# main.net
KiCad netlist of a schematic drawn in EAGLE
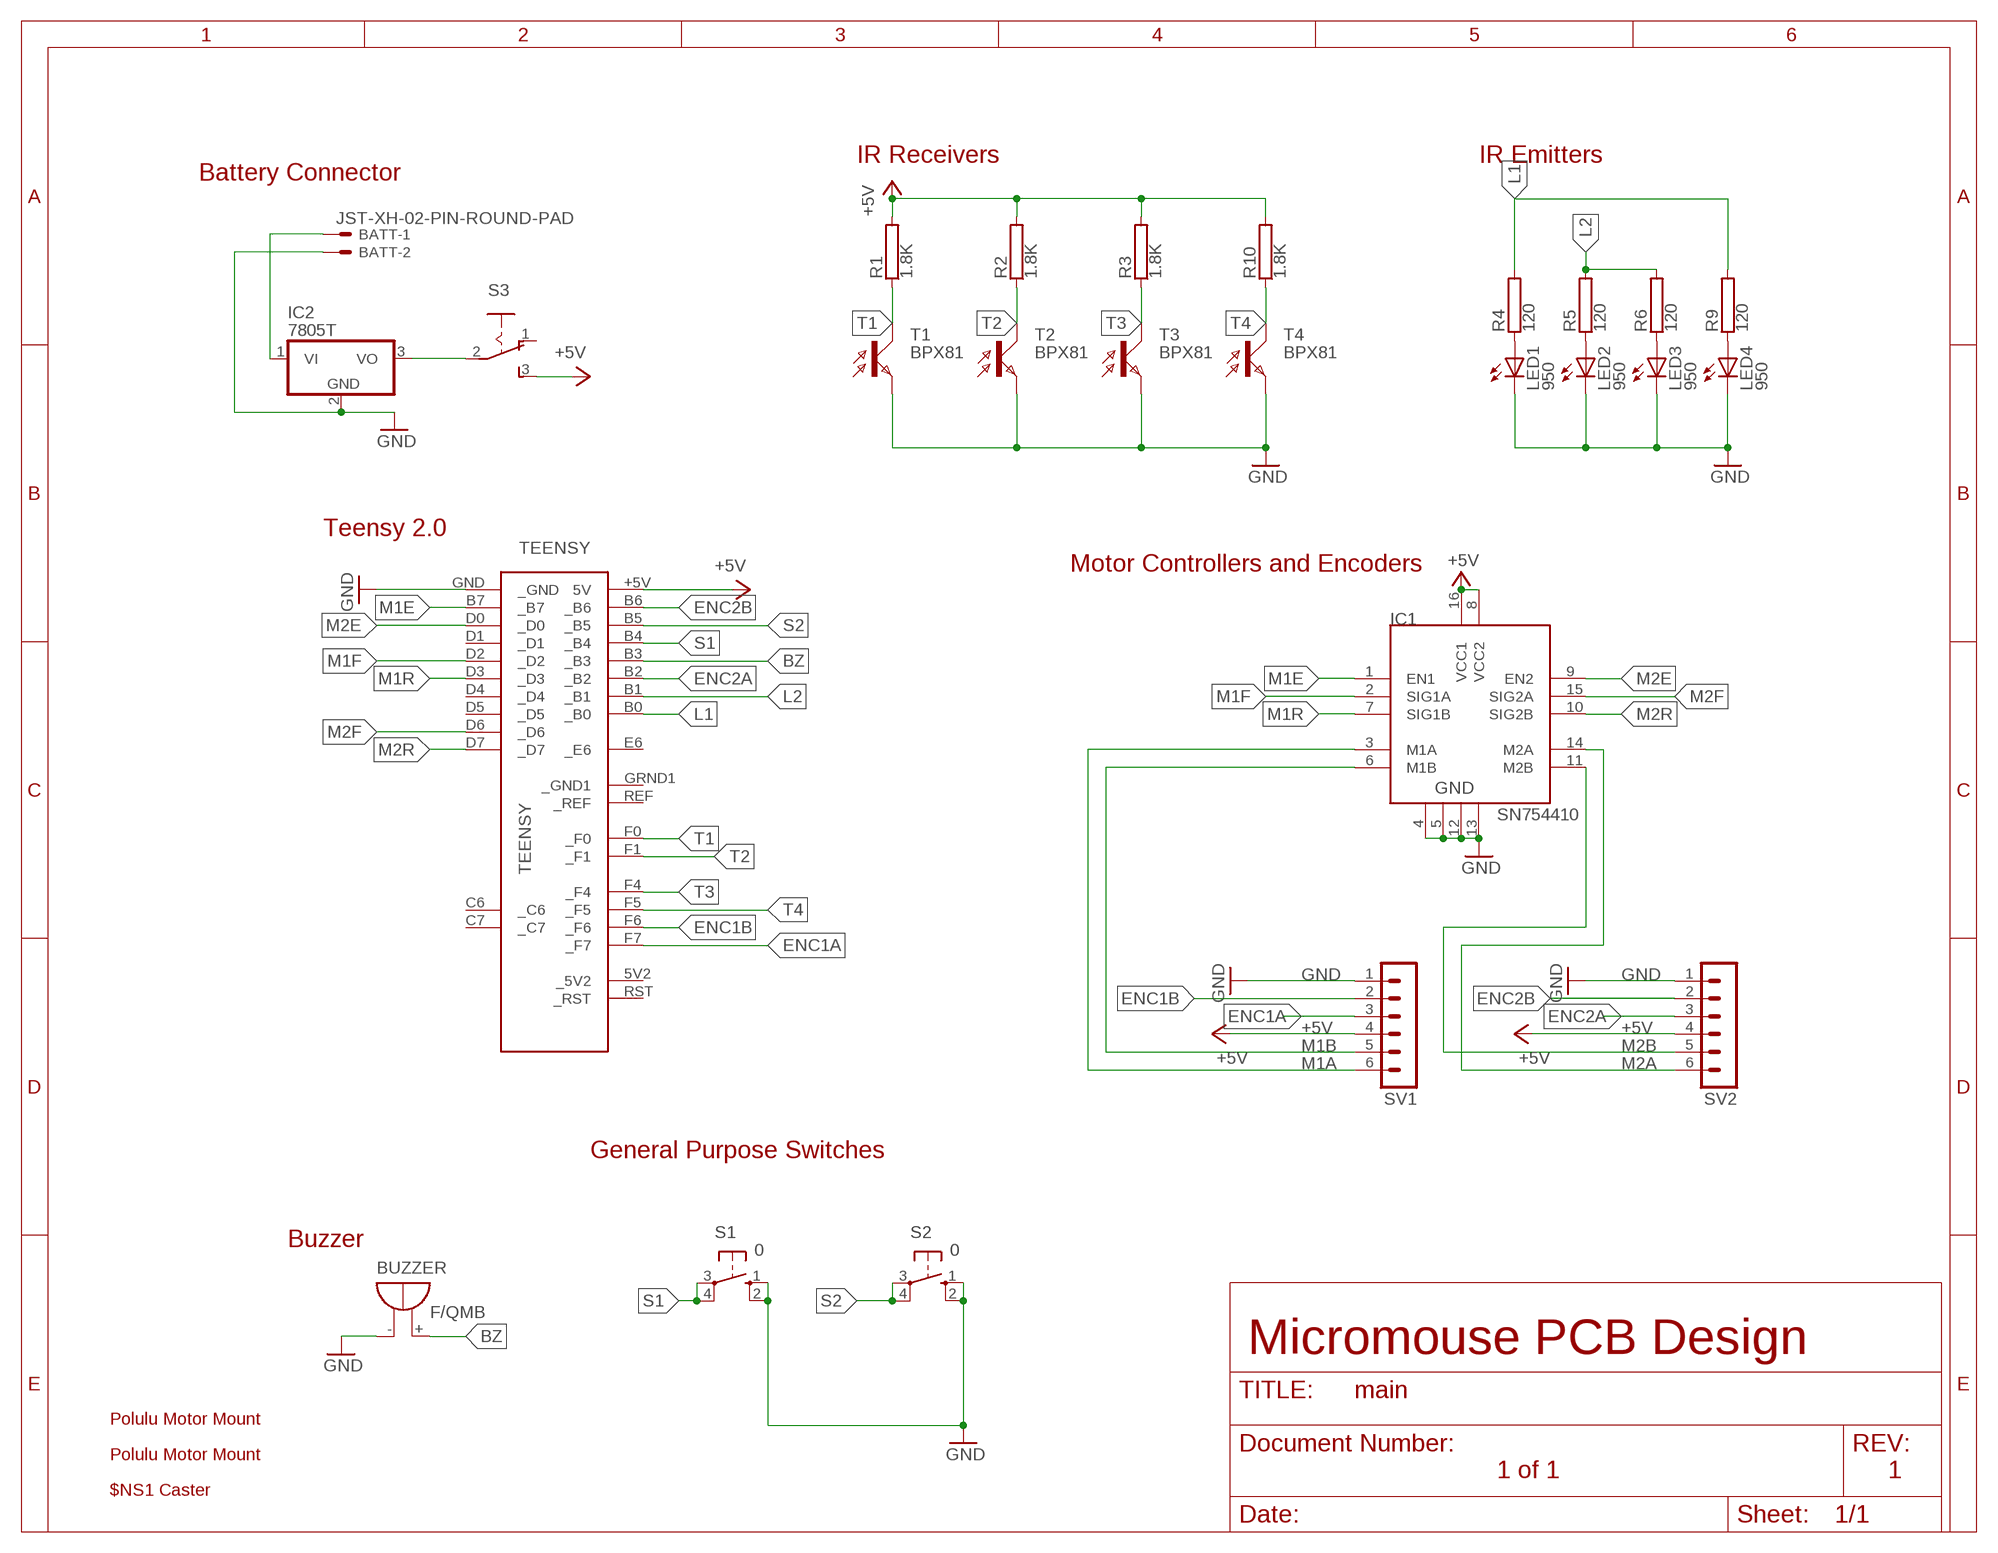
[diagram p0: schematic, sheet 1]

(export (version "E")
  (design (tool "Eeschema 10.0.6"))
  (components
    (comp (ref "BATT")
      (value "JST-XH-02-PIN-ROUND-PAD")
      (footprint "eagle-import:JST-XH-02-PACKAGE-ROUND-PAD")
      (fields (field (name "OC_NEWARK") "unknown"))
      (libsource (lib "eagle-import") (part "JST-XH-02-PIN-ROUND-PAD"))
    )
    (comp (ref "BUZZER")
      (value "F/QMB")
      (footprint "eagle-import:F_QMB")
      (libsource (lib "eagle-import") (part "F/QMB"))
    )
    (comp (ref "IC1")
      (value "SN754410")
      (footprint "eagle-import:DIP16")
      (fields (field (name "MF") "TEXAS INSTRUMENTS") (field (name "MPN") "SN754410NE"))
      (libsource (lib "eagle-import") (part "SN754410"))
    )
    (comp (ref "IC2")
      (value "7805T")
      (footprint "eagle-import:TO220H")
      (fields (field (name "MPN") "NCP7805TG"))
      (libsource (lib "eagle-import") (part "78T05"))
    )
    (comp (ref "LED1")
      (value "950")
      (footprint "eagle-import:LED3MM")
      (fields (field (name "MPN") "CNX_B_E_4_1_04"))
      (libsource (lib "eagle-import") (part "LED3MM"))
    )
    (comp (ref "LED2")
      (value "950")
      (footprint "eagle-import:LED3MM")
      (fields (field (name "MPN") "CNX_B_E_4_1_04"))
      (libsource (lib "eagle-import") (part "LED3MM"))
    )
    (comp (ref "LED3")
      (value "950")
      (footprint "eagle-import:LED3MM")
      (fields (field (name "MPN") "CNX_B_E_4_1_04"))
      (libsource (lib "eagle-import") (part "LED3MM"))
    )
    (comp (ref "LED4")
      (value "950")
      (footprint "eagle-import:LED3MM")
      (fields (field (name "MPN") "CNX_B_E_4_1_04"))
      (libsource (lib "eagle-import") (part "LED3MM"))
    )
    (comp (ref "R1")
      (value "1.8K")
      (footprint "eagle-import:RS1_4")
      (fields (field (name "MF") "OHMITE") (field (name "MPN") "RRS1K0"))
      (libsource (lib "eagle-import") (part "RRS1/4"))
    )
    (comp (ref "R2")
      (value "1.8K")
      (footprint "eagle-import:RS1_4")
      (fields (field (name "MF") "OHMITE") (field (name "MPN") "RRS1K0"))
      (libsource (lib "eagle-import") (part "RRS1/4"))
    )
    (comp (ref "R3")
      (value "1.8K")
      (footprint "eagle-import:RS1_4")
      (fields (field (name "MF") "OHMITE") (field (name "MPN") "RRS1K0"))
      (libsource (lib "eagle-import") (part "RRS1/4"))
    )
    (comp (ref "R4")
      (value "120")
      (footprint "eagle-import:RS1_4")
      (fields (field (name "MF") "OHMITE") (field (name "MPN") "RRS1K0"))
      (libsource (lib "eagle-import") (part "RRS1/4"))
    )
    (comp (ref "R5")
      (value "120")
      (footprint "eagle-import:RS1_4")
      (fields (field (name "MF") "OHMITE") (field (name "MPN") "RRS1K0"))
      (libsource (lib "eagle-import") (part "RRS1/4"))
    )
    (comp (ref "R6")
      (value "120")
      (footprint "eagle-import:RS1_4")
      (fields (field (name "MF") "OHMITE") (field (name "MPN") "RRS1K0"))
      (libsource (lib "eagle-import") (part "RRS1/4"))
    )
    (comp (ref "R9")
      (value "120")
      (footprint "eagle-import:RS1_4")
      (fields (field (name "MF") "OHMITE") (field (name "MPN") "RRS1K0"))
      (libsource (lib "eagle-import") (part "RRS1/4"))
    )
    (comp (ref "R10")
      (value "1.8K")
      (footprint "eagle-import:RS1_4")
      (fields (field (name "MF") "OHMITE") (field (name "MPN") "RRS1K0"))
      (libsource (lib "eagle-import") (part "RRS1/4"))
    )
    (comp (ref "S1")
      (value "0")
      (footprint "eagle-import:B3F-10XX")
      (fields (field (name "MPN") "B3F-1000") (field (name "OC_NEWARK") "unknown"))
      (libsource (lib "eagle-import") (part "10-XX"))
    )
    (comp (ref "S2")
      (value "0")
      (footprint "eagle-import:B3F-10XX")
      (fields (field (name "MPN") "B3F-1000") (field (name "OC_NEWARK") "unknown"))
      (libsource (lib "eagle-import") (part "10-XX"))
    )
    (comp (ref "S3")
      (value "255SB")
      (footprint "eagle-import:255SB")
      (libsource (lib "eagle-import") (part "255SB"))
    )
    (comp (ref "SV1")
      (value "MA06-1")
      (footprint "eagle-import:MA06-1")
      (libsource (lib "eagle-import") (part "MA06-1"))
    )
    (comp (ref "SV2")
      (value "MA06-1")
      (footprint "eagle-import:MA06-1")
      (libsource (lib "eagle-import") (part "MA06-1"))
    )
    (comp (ref "T1")
      (value "BPX81")
      (footprint "eagle-import:BPX81")
      (libsource (lib "eagle-import") (part "BPX81"))
    )
    (comp (ref "T2")
      (value "BPX81")
      (footprint "eagle-import:BPX81")
      (libsource (lib "eagle-import") (part "BPX81"))
    )
    (comp (ref "T3")
      (value "BPX81")
      (footprint "eagle-import:BPX81")
      (libsource (lib "eagle-import") (part "BPX81"))
    )
    (comp (ref "T4")
      (value "BPX81")
      (footprint "eagle-import:BPX81")
      (libsource (lib "eagle-import") (part "BPX81"))
    )
    (comp (ref "TEENSY")
      (value "TEENSY")
      (footprint "eagle-import:TEENSY")
      (libsource (lib "eagle-import") (part "TEENSY"))
    )
    (comp (ref "U$1")
      (value "POLULUMOTOR")
      (footprint "eagle-import:FP")
      (libsource (lib "eagle-import") (part "POLULUMOTOR"))
    )
    (comp (ref "U$2")
      (value "POLULUMOTOR")
      (footprint "eagle-import:FP")
      (libsource (lib "eagle-import") (part "POLULUMOTOR"))
    )
    (comp (ref "U$3")
      (value "CASTERBALL")
      (footprint "eagle-import:FB_CASTER")
      (libsource (lib "eagle-import") (part "CASTERBALL"))
    )
  )
  (nets
    (net (code "1") (name "+5V") (class "Default")
      (node (ref "IC1") (pin "16") (pinfunction "VCC1_16") (pintype "power_in"))
      (node (ref "IC1") (pin "8") (pinfunction "VCC2_8") (pintype "power_in"))
      (node (ref "R1") (pin "2") (pinfunction "2_2") (pintype "passive"))
      (node (ref "R10") (pin "2") (pinfunction "2_2") (pintype "passive"))
      (node (ref "R2") (pin "2") (pinfunction "2_2") (pintype "passive"))
      (node (ref "R3") (pin "2") (pinfunction "2_2") (pintype "passive"))
      (node (ref "S3") (pin "3") (pinfunction "S_3") (pintype "passive"))
      (node (ref "SV1") (pin "4") (pinfunction "4_4") (pintype "passive"))
      (node (ref "SV2") (pin "4") (pinfunction "4_4") (pintype "passive"))
      (node (ref "TEENSY") (pin "+5V") (pinfunction "5V_+5V") (pintype "bidirectional"))
    )
    (net (code "2") (name "/M1A") (class "Default")
      (node (ref "IC1") (pin "3") (pinfunction "M1A_3") (pintype "bidirectional"))
      (node (ref "SV1") (pin "6") (pinfunction "6_6") (pintype "passive"))
    )
    (net (code "3") (name "/M1B") (class "Default")
      (node (ref "IC1") (pin "6") (pinfunction "M1B_6") (pintype "bidirectional"))
      (node (ref "SV1") (pin "5") (pinfunction "5_5") (pintype "passive"))
    )
    (net (code "4") (name "/M2A") (class "Default")
      (node (ref "IC1") (pin "14") (pinfunction "M2A_14") (pintype "bidirectional"))
      (node (ref "SV2") (pin "6") (pinfunction "6_6") (pintype "passive"))
    )
    (net (code "5") (name "/M2B") (class "Default")
      (node (ref "IC1") (pin "11") (pinfunction "M2B_11") (pintype "bidirectional"))
      (node (ref "SV2") (pin "5") (pinfunction "5_5") (pintype "passive"))
    )
    (net (code "6") (name "BZ") (class "Default")
      (node (ref "BUZZER") (pin "+") (pinfunction "-_+") (pintype "passive"))
      (node (ref "TEENSY") (pin "B3") (pinfunction "_B3_B3") (pintype "bidirectional"))
    )
    (net (code "7") (name "ENC1A") (class "Default")
      (node (ref "SV1") (pin "3") (pinfunction "3_3") (pintype "passive"))
      (node (ref "TEENSY") (pin "F7") (pinfunction "_F7_F7") (pintype "bidirectional"))
    )
    (net (code "8") (name "ENC1B") (class "Default")
      (node (ref "SV1") (pin "2") (pinfunction "2_2") (pintype "passive"))
      (node (ref "TEENSY") (pin "F6") (pinfunction "_F6_F6") (pintype "bidirectional"))
    )
    (net (code "9") (name "ENC2A") (class "Default")
      (node (ref "SV2") (pin "3") (pinfunction "3_3") (pintype "passive"))
      (node (ref "TEENSY") (pin "B2") (pinfunction "_B2_B2") (pintype "bidirectional"))
    )
    (net (code "10") (name "ENC2B") (class "Default")
      (node (ref "SV2") (pin "2") (pinfunction "2_2") (pintype "passive"))
      (node (ref "TEENSY") (pin "B6") (pinfunction "_B6_B6") (pintype "bidirectional"))
    )
    (net (code "11") (name "GND") (class "Default")
      (node (ref "BATT") (pin "2") (pinfunction "S_2") (pintype "passive"))
      (node (ref "BUZZER") (pin "-") (pinfunction "+_-") (pintype "passive"))
      (node (ref "IC1") (pin "12") (pinfunction "P12_12") (pintype "power_in"))
      (node (ref "IC1") (pin "13") (pinfunction "P13_13") (pintype "power_in"))
      (node (ref "IC1") (pin "4") (pinfunction "P4_4") (pintype "power_in"))
      (node (ref "IC1") (pin "5") (pinfunction "P5_5") (pintype "power_in"))
      (node (ref "IC2") (pin "2") (pinfunction "GND_2") (pintype "passive"))
      (node (ref "LED1") (pin "K") (pinfunction "C_K") (pintype "passive"))
      (node (ref "LED2") (pin "K") (pinfunction "C_K") (pintype "passive"))
      (node (ref "LED3") (pin "K") (pinfunction "C_K") (pintype "passive"))
      (node (ref "LED4") (pin "K") (pinfunction "C_K") (pintype "passive"))
      (node (ref "S1") (pin "1") (pinfunction "S_1") (pintype "passive"))
      (node (ref "S1") (pin "2") (pinfunction "S1_2") (pintype "passive"))
      (node (ref "S2") (pin "1") (pinfunction "S_1") (pintype "passive"))
      (node (ref "S2") (pin "2") (pinfunction "S1_2") (pintype "passive"))
      (node (ref "SV1") (pin "1") (pinfunction "1_1") (pintype "passive"))
      (node (ref "SV2") (pin "1") (pinfunction "1_1") (pintype "passive"))
      (node (ref "T1") (pin "E") (pinfunction "E_E") (pintype "passive"))
      (node (ref "T2") (pin "E") (pinfunction "E_E") (pintype "passive"))
      (node (ref "T3") (pin "E") (pinfunction "E_E") (pintype "passive"))
      (node (ref "T4") (pin "E") (pinfunction "E_E") (pintype "passive"))
      (node (ref "TEENSY") (pin "GND") (pinfunction "_GND_GND") (pintype "bidirectional"))
    )
    (net (code "12") (name "L1") (class "Default")
      (node (ref "R4") (pin "2") (pinfunction "2_2") (pintype "passive"))
      (node (ref "R9") (pin "2") (pinfunction "2_2") (pintype "passive"))
      (node (ref "TEENSY") (pin "B0") (pinfunction "_B0_B0") (pintype "bidirectional"))
    )
    (net (code "13") (name "L2") (class "Default")
      (node (ref "R5") (pin "2") (pinfunction "2_2") (pintype "passive"))
      (node (ref "R6") (pin "2") (pinfunction "2_2") (pintype "passive"))
      (node (ref "TEENSY") (pin "B1") (pinfunction "_B1_B1") (pintype "bidirectional"))
    )
    (net (code "14") (name "M1E") (class "Default")
      (node (ref "IC1") (pin "1") (pinfunction "EN1_1") (pintype "bidirectional"))
      (node (ref "TEENSY") (pin "B7") (pinfunction "_B7_B7") (pintype "bidirectional"))
    )
    (net (code "15") (name "M1F") (class "Default")
      (node (ref "IC1") (pin "2") (pinfunction "SIG1A_2") (pintype "bidirectional"))
      (node (ref "TEENSY") (pin "D2") (pinfunction "_D2_D2") (pintype "bidirectional"))
    )
    (net (code "16") (name "M1R") (class "Default")
      (node (ref "IC1") (pin "7") (pinfunction "SIG1B_7") (pintype "bidirectional"))
      (node (ref "TEENSY") (pin "D3") (pinfunction "_D3_D3") (pintype "bidirectional"))
    )
    (net (code "17") (name "M2E") (class "Default")
      (node (ref "IC1") (pin "9") (pinfunction "EN2_9") (pintype "bidirectional"))
      (node (ref "TEENSY") (pin "D0") (pinfunction "_D0_D0") (pintype "bidirectional"))
    )
    (net (code "18") (name "M2F") (class "Default")
      (node (ref "IC1") (pin "15") (pinfunction "SIG2A_15") (pintype "bidirectional"))
      (node (ref "TEENSY") (pin "D6") (pinfunction "_D6_D6") (pintype "bidirectional"))
    )
    (net (code "19") (name "M2R") (class "Default")
      (node (ref "IC1") (pin "10") (pinfunction "SIG2B_10") (pintype "bidirectional"))
      (node (ref "TEENSY") (pin "D7") (pinfunction "_D7_D7") (pintype "bidirectional"))
    )
    (net (code "20") (name "Net-(BATTA-S)") (class "Default")
      (node (ref "BATT") (pin "1") (pinfunction "S_1") (pintype "passive"))
      (node (ref "IC2") (pin "1") (pinfunction "VI_1") (pintype "input"))
    )
    (net (code "21") (name "Net-(IC2-VO)") (class "Default")
      (node (ref "IC2") (pin "3") (pinfunction "VO_3") (pintype "passive"))
      (node (ref "S3") (pin "2") (pinfunction "P_2") (pintype "passive"))
    )
    (net (code "22") (name "Net-(LED1-PadA)") (class "Default")
      (node (ref "LED1") (pin "A") (pinfunction "A_A") (pintype "passive"))
      (node (ref "R4") (pin "1") (pinfunction "1_1") (pintype "passive"))
    )
    (net (code "23") (name "Net-(LED2-PadA)") (class "Default")
      (node (ref "LED2") (pin "A") (pinfunction "A_A") (pintype "passive"))
      (node (ref "R5") (pin "1") (pinfunction "1_1") (pintype "passive"))
    )
    (net (code "24") (name "Net-(LED3-PadA)") (class "Default")
      (node (ref "LED3") (pin "A") (pinfunction "A_A") (pintype "passive"))
      (node (ref "R6") (pin "1") (pinfunction "1_1") (pintype "passive"))
    )
    (net (code "25") (name "Net-(LED4-PadA)") (class "Default")
      (node (ref "LED4") (pin "A") (pinfunction "A_A") (pintype "passive"))
      (node (ref "R9") (pin "1") (pinfunction "1_1") (pintype "passive"))
    )
    (net (code "26") (name "S1") (class "Default")
      (node (ref "S1") (pin "3") (pinfunction "P_3") (pintype "passive"))
      (node (ref "S1") (pin "4") (pinfunction "P1_4") (pintype "passive"))
      (node (ref "TEENSY") (pin "B4") (pinfunction "_B4_B4") (pintype "bidirectional"))
    )
    (net (code "27") (name "S2") (class "Default")
      (node (ref "S2") (pin "3") (pinfunction "P_3") (pintype "passive"))
      (node (ref "S2") (pin "4") (pinfunction "P1_4") (pintype "passive"))
      (node (ref "TEENSY") (pin "B5") (pinfunction "_B5_B5") (pintype "bidirectional"))
    )
    (net (code "28") (name "T1") (class "Default")
      (node (ref "R1") (pin "1") (pinfunction "1_1") (pintype "passive"))
      (node (ref "T1") (pin "C") (pinfunction "C_C") (pintype "passive"))
      (node (ref "TEENSY") (pin "F0") (pinfunction "_F0_F0") (pintype "bidirectional"))
    )
    (net (code "29") (name "T2") (class "Default")
      (node (ref "R2") (pin "1") (pinfunction "1_1") (pintype "passive"))
      (node (ref "T2") (pin "C") (pinfunction "C_C") (pintype "passive"))
      (node (ref "TEENSY") (pin "F1") (pinfunction "_F1_F1") (pintype "bidirectional"))
    )
    (net (code "30") (name "T3") (class "Default")
      (node (ref "R3") (pin "1") (pinfunction "1_1") (pintype "passive"))
      (node (ref "T3") (pin "C") (pinfunction "C_C") (pintype "passive"))
      (node (ref "TEENSY") (pin "F4") (pinfunction "_F4_F4") (pintype "bidirectional"))
    )
    (net (code "31") (name "T4") (class "Default")
      (node (ref "R10") (pin "1") (pinfunction "1_1") (pintype "passive"))
      (node (ref "T4") (pin "C") (pinfunction "C_C") (pintype "passive"))
      (node (ref "TEENSY") (pin "F5") (pinfunction "_F5_F5") (pintype "bidirectional"))
    )
    (net (code "32") (name "unconnected-(S3-O-Pad1)") (class "Default")
      (node (ref "S3") (pin "1") (pinfunction "O_1") (pintype "passive"))
    )
    (net (code "33") (name "unconnected-(TEENSY-_5V2-Pad5V2)") (class "Default")
      (node (ref "TEENSY") (pin "5V2") (pinfunction "_5V2_5V2") (pintype "bidirectional"))
    )
    (net (code "34") (name "unconnected-(TEENSY-_C6-PadC6)") (class "Default")
      (node (ref "TEENSY") (pin "C6") (pinfunction "_C6_C6") (pintype "bidirectional"))
    )
    (net (code "35") (name "unconnected-(TEENSY-_C7-PadC7)") (class "Default")
      (node (ref "TEENSY") (pin "C7") (pinfunction "_C7_C7") (pintype "bidirectional"))
    )
    (net (code "36") (name "unconnected-(TEENSY-_D1-PadD1)") (class "Default")
      (node (ref "TEENSY") (pin "D1") (pinfunction "_D1_D1") (pintype "bidirectional"))
    )
    (net (code "37") (name "unconnected-(TEENSY-_D4-PadD4)") (class "Default")
      (node (ref "TEENSY") (pin "D4") (pinfunction "_D4_D4") (pintype "bidirectional"))
    )
    (net (code "38") (name "unconnected-(TEENSY-_D5-PadD5)") (class "Default")
      (node (ref "TEENSY") (pin "D5") (pinfunction "_D5_D5") (pintype "bidirectional"))
    )
    (net (code "39") (name "unconnected-(TEENSY-_E6-PadE6)") (class "Default")
      (node (ref "TEENSY") (pin "E6") (pinfunction "_E6_E6") (pintype "bidirectional"))
    )
    (net (code "40") (name "unconnected-(TEENSY-_GND1-PadGRND1)") (class "Default")
      (node (ref "TEENSY") (pin "GRND1") (pinfunction "_GND1_GRND1") (pintype "bidirectional"))
    )
    (net (code "41") (name "unconnected-(TEENSY-_REF-PadREF)") (class "Default")
      (node (ref "TEENSY") (pin "REF") (pinfunction "_REF_REF") (pintype "bidirectional"))
    )
    (net (code "42") (name "unconnected-(TEENSY-_RST-PadRST)") (class "Default")
      (node (ref "TEENSY") (pin "RST") (pinfunction "_RST_RST") (pintype "bidirectional"))
    )
  )
)
